# main.net
KiCad netlist of a schematic drawn in EAGLE
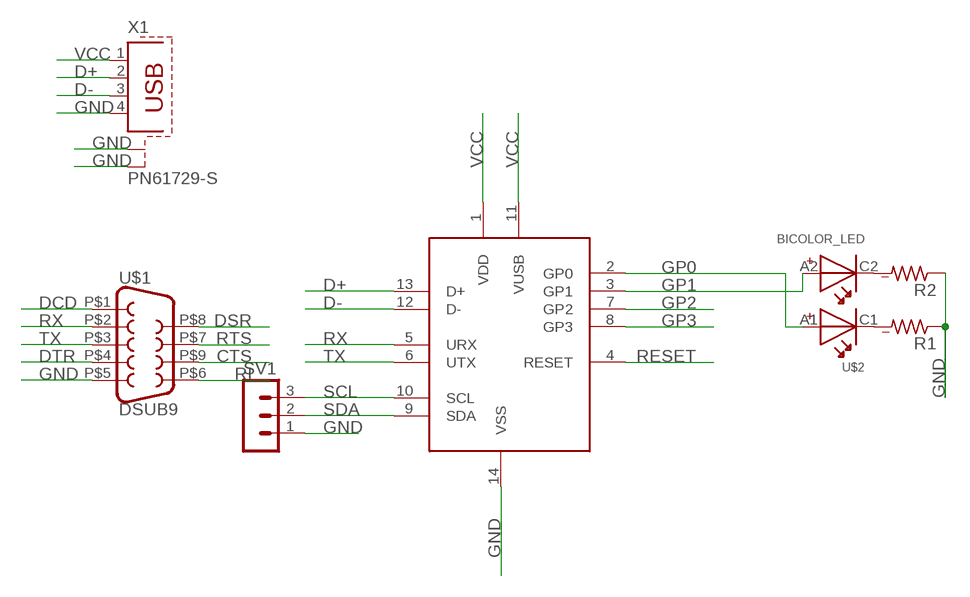
[diagram p0: schematic, sheet 1]

(export (version "E")
  (design (tool "Eeschema 10.0.6"))
  (components
    (comp (ref "BR1")
      (value "MCP2221A")
      (footprint "eagle-import:DIP14")
      (libsource (lib "eagle-import") (part "MCP2221A"))
    )
    (comp (ref "R1")
      (value "R-US_M0805")
      (footprint "eagle-import:M0805")
      (libsource (lib "eagle-import") (part "R-US_M0805"))
    )
    (comp (ref "R2")
      (value "R-US_M0805")
      (footprint "eagle-import:M0805")
      (libsource (lib "eagle-import") (part "R-US_M0805"))
    )
    (comp (ref "SV1")
      (value "MA03-1")
      (footprint "eagle-import:MA03-1")
      (libsource (lib "eagle-import") (part "MA03-1"))
    )
    (comp (ref "U$1")
      (value "DSUB9")
      (footprint "eagle-import:DSUB9_EDGECARD")
      (libsource (lib "eagle-import") (part "DSUB9"))
    )
    (comp (ref "U$2")
      (value "BICOLOR_LED")
      (footprint "eagle-import:BICOLOR_LED")
      (libsource (lib "eagle-import") (part "BICOLOR_LED"))
    )
    (comp (ref "X1")
      (value "PN61729-S")
      (footprint "eagle-import:PN61729-S")
      (libsource (lib "eagle-import") (part "PN61729-S"))
    )
  )
  (nets
    (net (code "1") (name "/CTS") (class "Default")
      (node (ref "U$1") (pin "P$9") (pinfunction "CTS_P$9") (pintype "passive"))
    )
    (net (code "2") (name "/D+") (class "Default")
      (node (ref "BR1") (pin "13") (pinfunction "D+_13") (pintype "bidirectional"))
      (node (ref "X1") (pin "2") (pinfunction "2_2") (pintype "passive"))
    )
    (net (code "3") (name "/D-") (class "Default")
      (node (ref "BR1") (pin "12") (pinfunction "D-_12") (pintype "bidirectional"))
      (node (ref "X1") (pin "3") (pinfunction "3_3") (pintype "passive"))
    )
    (net (code "4") (name "/DCD") (class "Default")
      (node (ref "U$1") (pin "P$1") (pinfunction "DCD_P$1") (pintype "passive"))
    )
    (net (code "5") (name "/DSR") (class "Default")
      (node (ref "U$1") (pin "P$8") (pinfunction "DSR_P$8") (pintype "passive"))
    )
    (net (code "6") (name "/DTR") (class "Default")
      (node (ref "U$1") (pin "P$4") (pinfunction "DTR_P$4") (pintype "passive"))
    )
    (net (code "7") (name "/GND") (class "Default")
      (node (ref "BR1") (pin "14") (pinfunction "VSS_14") (pintype "bidirectional"))
      (node (ref "R1") (pin "1") (pinfunction "1_1") (pintype "passive"))
      (node (ref "R2") (pin "1") (pinfunction "1_1") (pintype "passive"))
      (node (ref "SV1") (pin "1") (pinfunction "1_1") (pintype "passive"))
      (node (ref "U$1") (pin "P$5") (pinfunction "GND_P$5") (pintype "passive"))
      (node (ref "X1") (pin "4") (pinfunction "4_4") (pintype "passive"))
      (node (ref "X1") (pin "S1") (pinfunction "S1_S1") (pintype "passive"))
      (node (ref "X1") (pin "S2") (pinfunction "S2_S2") (pintype "passive"))
    )
    (net (code "8") (name "/GP0") (class "Default")
      (node (ref "BR1") (pin "2") (pinfunction "GP0_2") (pintype "bidirectional"))
      (node (ref "U$2") (pin "A1") (pinfunction "A1_A1") (pintype "passive"))
    )
    (net (code "9") (name "/GP1") (class "Default")
      (node (ref "BR1") (pin "3") (pinfunction "GP1_3") (pintype "bidirectional"))
      (node (ref "U$2") (pin "A2") (pinfunction "A2_A2") (pintype "passive"))
    )
    (net (code "10") (name "/GP2") (class "Default")
      (node (ref "BR1") (pin "7") (pinfunction "GP2_7") (pintype "bidirectional"))
    )
    (net (code "11") (name "/GP3") (class "Default")
      (node (ref "BR1") (pin "8") (pinfunction "GP3_8") (pintype "bidirectional"))
    )
    (net (code "12") (name "/RESET") (class "Default")
      (node (ref "BR1") (pin "4") (pinfunction "RESET_4") (pintype "bidirectional"))
    )
    (net (code "13") (name "/RI") (class "Default")
      (node (ref "U$1") (pin "P$6") (pinfunction "RI_P$6") (pintype "passive"))
    )
    (net (code "14") (name "/RTS") (class "Default")
      (node (ref "U$1") (pin "P$7") (pinfunction "RTS_P$7") (pintype "passive"))
    )
    (net (code "15") (name "/RX") (class "Default")
      (node (ref "BR1") (pin "5") (pinfunction "URX_5") (pintype "bidirectional"))
      (node (ref "U$1") (pin "P$2") (pinfunction "RXD_P$2") (pintype "passive"))
    )
    (net (code "16") (name "/SCL") (class "Default")
      (node (ref "BR1") (pin "10") (pinfunction "SCL_10") (pintype "bidirectional"))
      (node (ref "SV1") (pin "3") (pinfunction "3_3") (pintype "passive"))
    )
    (net (code "17") (name "/SDA") (class "Default")
      (node (ref "BR1") (pin "9") (pinfunction "SDA_9") (pintype "bidirectional"))
      (node (ref "SV1") (pin "2") (pinfunction "2_2") (pintype "passive"))
    )
    (net (code "18") (name "/TX") (class "Default")
      (node (ref "BR1") (pin "6") (pinfunction "UTX_6") (pintype "bidirectional"))
      (node (ref "U$1") (pin "P$3") (pinfunction "TXD_P$3") (pintype "passive"))
    )
    (net (code "19") (name "/VCC") (class "Default")
      (node (ref "BR1") (pin "1") (pinfunction "VDD_1") (pintype "bidirectional"))
      (node (ref "BR1") (pin "11") (pinfunction "VUSB_11") (pintype "bidirectional"))
      (node (ref "X1") (pin "1") (pinfunction "1_1") (pintype "passive"))
    )
    (net (code "20") (name "Net-(R1-Pad2)") (class "Default")
      (node (ref "R1") (pin "2") (pinfunction "2_2") (pintype "passive"))
      (node (ref "U$2") (pin "C1") (pinfunction "C1_C1") (pintype "passive"))
    )
    (net (code "21") (name "Net-(R2-Pad2)") (class "Default")
      (node (ref "R2") (pin "2") (pinfunction "2_2") (pintype "passive"))
      (node (ref "U$2") (pin "C2") (pinfunction "C2_C2") (pintype "passive"))
    )
  )
)
